# Power_LCD.net
KiCad netlist of a schematic drawn in Altium Designer
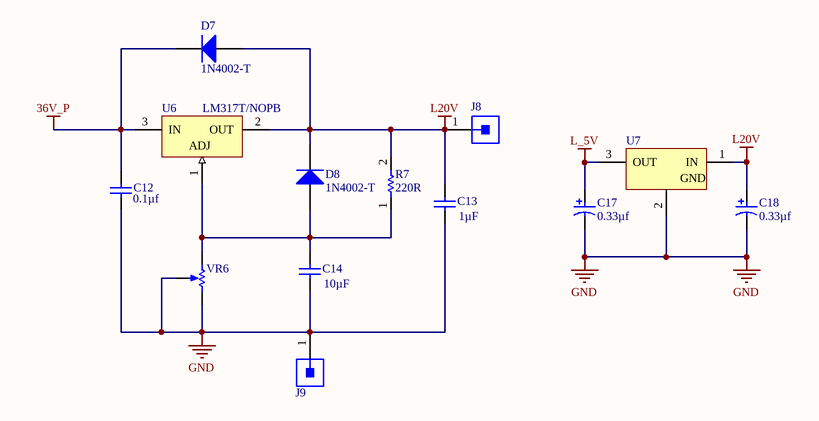
[diagram p0: Power_LCD.SchDoc]

(export (version "E")
  (design (tool "Eeschema 10.0.6"))
  (components
    (comp (ref "C12")
      (value "0.1µf")
      (footprint "Cap-0.1uf-50V-Ceramic1")
      (description "Lead Capacitor X7R_EIA_ with Capacitance: 0.10F and Rated Voltage: 50Vdc")
      (fields (field (name "MP") "RDER71H104K0K1H03B") (field (name "MF") "Murata"))
      (libsource (lib "YAYAT-LIB") (part "Cap-0.1uf-50V-Ceramic_1"))
    )
    (comp (ref "C13")
      (value "K104K15X7RF5TL2")
      (footprint "Cap-0.1uf-50v-ceramic")
      (description "Ceramic Capacitor, 100 nF, +/- 10%, 50 V, -55 to 125 degC, 2-Pin THD, RoHS, Tape and Reel")
      (fields
        (field (name "MANUFACTURER") "Vishay")
        (field (name "TOLERANCE") "±10%")
        (field (name "CAPACITANCE") "1µF")
      )
      (libsource (lib "YAYAT-LIB") (part "Cap-0.1uf-50v-ceramic"))
    )
    (comp (ref "C14")
      (value "K104K15X7RF5TL2")
      (footprint "Cap-0.1uf-50v-ceramic")
      (description "Ceramic Capacitor, 100 nF, +/- 10%, 50 V, -55 to 125 degC, 2-Pin THD, RoHS, Tape and Reel")
      (fields
        (field (name "MANUFACTURER") "Vishay")
        (field (name "TOLERANCE") "±10%")
        (field (name "CAPACITANCE") "10µF")
      )
      (libsource (lib "YAYAT-LIB") (part "Cap-0.1uf-50v-ceramic"))
    )
    (comp (ref "C17")
      (value "0.33µf")
      (footprint "Cap-1uf-50v-radial")
      (description "Aluminum Electrolytic Capacitor, 1 uF, +/- 20%, 50 V, -55 to 105 degC, 2-Pin THD, RoHS, Bulk")
      (libsource (lib "YAYAT-LIB") (part "Cap-1uf-50v-radial"))
    )
    (comp (ref "C18")
      (value "0.33µf")
      (footprint "Cap-1uf-50v-radial")
      (description "Aluminum Electrolytic Capacitor, 1 uF, +/- 20%, 50 V, -55 to 105 degC, 2-Pin THD, RoHS, Bulk")
      (libsource (lib "YAYAT-LIB") (part "Cap-1uf-50v-radial"))
    )
    (comp (ref "D7")
      (value "1N4002-T")
      (footprint "Diode-1N4002")
      (description "1.0 A Rectifier, 15 pF, 100 V, -65 to 150 degC, 2-Pin DO-41 Plastic, RoHS, Tape and Reel")
      (fields (field (name "MANUFACTURER") "Diodes Inc"))
      (libsource (lib "YAYAT-LIB") (part "Diode-1N4002"))
    )
    (comp (ref "D8")
      (value "1N4002-T")
      (footprint "Diode-1N4002")
      (description "1.0 A Rectifier, 15 pF, 100 V, -65 to 150 degC, 2-Pin DO-41 Plastic, RoHS, Tape and Reel")
      (fields (field (name "MANUFACTURER") "Diodes Inc"))
      (libsource (lib "YAYAT-LIB") (part "Diode-1N4002"))
    )
    (comp (ref "J8")
      (value "61300111121")
      (footprint "PIN-HEADER-1PIN")
      (description "THT Vertical Pin Header WR-PHD, Pitch 2.54 mm, Single Row, 1 pins")
      (fields (field (name "MANUFACTURER") "Wurth Elektronik") (field (name "PUBLISHER") "WurthElektronik"))
      (libsource (lib "") (part "Pin-Header-1Pin_1"))
    )
    (comp (ref "J9")
      (value "61300111121")
      (footprint "PIN-HEADER-1PIN")
      (description "THT Vertical Pin Header WR-PHD, Pitch 2.54 mm, Single Row, 1 pins")
      (fields (field (name "MANUFACTURER") "Wurth Elektronik") (field (name "PUBLISHER") "WurthElektronik"))
      (libsource (lib "YAYAT-LIB") (part "Pin-Header-1Pin"))
    )
    (comp (ref "R7")
      (value "220R")
      (footprint "Resistor-1-Watt")
      (description "Resistor")
      (fields
        (field (name "MANUFACTURER_PART_NUMBER") "OK1025E-R52")
        (field (name "MOUSER PART NUMBER") "588-OK1025E-R52")
      )
      (libsource (lib "YAYAT-LIB") (part "Resistor-1-Watt"))
    )
    (comp (ref "U6")
      (value "LM317T/NOPB")
      (footprint "Voltage-Regulator-LM317")
      (description "3-Terminal Adjustable Regulator, 3-pin TO-220, Pb-Free")
      (fields (field (name "MANUFACTURER") "Texas Instruments"))
      (libsource (lib "YAYAT-LIB") (part "Voltage-Regulator-LM317"))
    )
    (comp (ref "U7")
      (value "L7805ACV")
      (footprint "Voltage-Regulator-L7805ACV")
      (description "Positive Voltage Regulator, 5V, 3-Pin TO-220")
      (libsource (lib "YAYAT-LIB") (part "Voltage-Regulator-L7805ACV"))
    )
    (comp (ref "VR6")
      (value "3296W-1-103LF")
      (footprint "Resistor-Trimmer")
      (fields (field (name "TOLERANCE") "1%"))
      (libsource (lib "YAYAT-LIB") (part "Resistor-Trimmer"))
    )
  )
  (nets
    (net (code "1") (name "36V_P") (class "Default")
      (node (ref "C12") (pin "2") (pinfunction "2_2") (pintype "passive"))
      (node (ref "D7") (pin "2") (pinfunction "K_2") (pintype "passive"))
      (node (ref "U6") (pin "3") (pinfunction "IN_3") (pintype "power_in"))
    )
    (net (code "2") (name "GND") (class "Default")
      (node (ref "C12") (pin "1") (pinfunction "1_1") (pintype "passive"))
      (node (ref "C13") (pin "1") (pinfunction "1_1") (pintype "passive"))
      (node (ref "C14") (pin "1") (pinfunction "1_1") (pintype "passive"))
      (node (ref "C17") (pin "2") (pinfunction "2_2") (pintype "passive"))
      (node (ref "C18") (pin "2") (pinfunction "2_2") (pintype "passive"))
      (node (ref "J9") (pin "1") (pinfunction "1_1") (pintype "passive"))
      (node (ref "U7") (pin "2") (pinfunction "GND_2") (pintype "power_in"))
      (node (ref "VR6") (pin "2") (pinfunction "S_2") (pintype "passive"))
      (node (ref "VR6") (pin "3") (pinfunction "CW_3") (pintype "passive"))
    )
    (net (code "3") (name "L20V") (class "Default")
      (node (ref "C13") (pin "2") (pinfunction "2_2") (pintype "passive"))
      (node (ref "C18") (pin "1") (pinfunction "1_1") (pintype "passive"))
      (node (ref "D7") (pin "1") (pinfunction "A_1") (pintype "passive"))
      (node (ref "D8") (pin "2") (pinfunction "K_2") (pintype "passive"))
      (node (ref "J8") (pin "1") (pinfunction "1_1") (pintype "passive"))
      (node (ref "R7") (pin "2") (pinfunction "2_2") (pintype "passive"))
      (node (ref "U6") (pin "2") (pinfunction "OUT_2") (pintype "power_in"))
      (node (ref "U7") (pin "1") (pinfunction "IN_1") (pintype "power_in"))
    )
    (net (code "4") (name "L_5V") (class "Default")
      (node (ref "C17") (pin "1") (pinfunction "1_1") (pintype "passive"))
      (node (ref "U7") (pin "3") (pinfunction "OUT_3") (pintype "power_in"))
    )
    (net (code "5") (name "Net-(D8-A)") (class "Default")
      (node (ref "C14") (pin "2") (pinfunction "2_2") (pintype "passive"))
      (node (ref "D8") (pin "1") (pinfunction "A_1") (pintype "passive"))
      (node (ref "R7") (pin "1") (pinfunction "1_1") (pintype "passive"))
      (node (ref "U6") (pin "1") (pinfunction "ADJ_1") (pintype "input"))
      (node (ref "VR6") (pin "1") (pinfunction "CCW_1") (pintype "passive"))
    )
  )
)
